# VREG_RT9166-13PVL_with_EN.net
KiCad netlist of a schematic drawn in Altium Designer
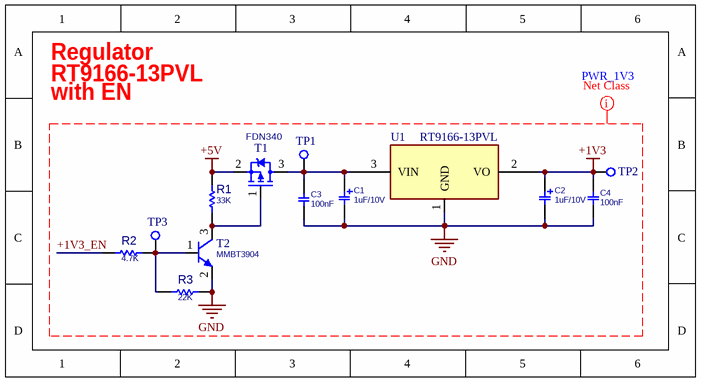
[diagram p0: VREG RT9166-13PVL with EN.SchDoc]

(export (version "E")
  (design (tool "Eeschema 10.0.6"))
  (components
    (comp (ref "C1")
      (value "1uF/10V")
      (footprint "C_TN_A")
      (description "CAP, SMD, TAN")
      (libsource (lib "PW Components 97_492") (part "CAP_SMD_TAN"))
    )
    (comp (ref "C2")
      (value "1uF/10V")
      (footprint "C_TN_A")
      (description "CAP, SMD, TAN")
      (libsource (lib "PW Components 97_492") (part "CAP_SMD_TAN"))
    )
    (comp (ref "C3")
      (value "100nF")
      (footprint "C0603S")
      (description "CAP, SMD, MLCC")
      (fields (field (name "MANF_P#") "MANF_PART#") (field (name "MANF") "Murata"))
      (libsource (lib "Passive") (part "CAP_SMD_MLCC"))
    )
    (comp (ref "C4")
      (value "100nF")
      (footprint "C0603S")
      (description "CAP, SMD, MLCC")
      (fields (field (name "MANF_P#") "MANF_PART#") (field (name "MANF") "Murata"))
      (libsource (lib "Passive") (part "CAP_SMD_MLCC"))
    )
    (comp (ref "R1")
      (value "33K")
      (footprint "R0603S")
      (description "RES, SMD")
      (fields (field (name "MANF_P#") "RK73H1ETTP4701F") (field (name "MANF") "KOA SPEER"))
      (libsource (lib "Passive") (part "RES_SMD"))
    )
    (comp (ref "R2")
      (value "4.7K")
      (footprint "R0603S")
      (description "RES, SMD")
      (fields (field (name "MANF_P#") "RK73H1ETTP4701F") (field (name "MANF") "KOA SPEER"))
      (libsource (lib "Passive") (part "RES_SMD"))
    )
    (comp (ref "R3")
      (value "22K")
      (footprint "R0603S")
      (description "RES, SMD")
      (fields (field (name "MANF_P#") "RK73H1ETTP4701F") (field (name "MANF") "KOA SPEER"))
      (libsource (lib "Passive") (part "RES_SMD"))
    )
    (comp (ref "T1")
      (value "FDN340")
      (footprint "SOT23_3")
      (description "MOSFET SMD P-CH 20V 2A")
      (fields (field (name "MANF_P#") "FDN360"))
      (libsource (lib "Transistor FET") (part "MOSP_FDN340_SOT23"))
    )
    (comp (ref "T2")
      (value "MMBT3904")
      (footprint "SOT23_3")
      (description "BJT, NPN, 40V, 0.2A, SMD, SOT23")
      (fields (field (name "MANF") "Diodes, NXP, FAIRCHILD, ON"))
      (libsource (lib "Transistor BJT") (part "NPN_MMBT3904_SOT23"))
    )
    (comp (ref "TP1")
      (value "Test Point")
      (footprint "TPSMD_C1")
      (libsource (lib "Passives") (part "Test Point"))
    )
    (comp (ref "TP2")
      (value "Test Point")
      (footprint "TPSMD_C1")
      (libsource (lib "Passives") (part "Test Point"))
    )
    (comp (ref "TP3")
      (value "Test Point")
      (footprint "TPSMD_C1")
      (libsource (lib "Passives") (part "Test Point"))
    )
    (comp (ref "U1")
      (value "RT9166-13PVL")
      (footprint "SOT23_3")
      (description "REG, Linear, Fixed, 1.3v, 0.3A/0.6A, SOT23")
      (fields (field (name "MANF") "TI"))
      (libsource (lib "PW Components 97_481") (part "VREG_RT9166A-13PVL_SOT23"))
    )
  )
  (nets
    (net (code "1") (name "+1V3") (class "Default")
      (node (ref "C2") (pin "1") (pinfunction "1_1") (pintype "passive"))
      (node (ref "C4") (pin "1") (pinfunction "1_1") (pintype "passive"))
      (node (ref "TP2") (pin "1") (pinfunction "TP_1") (pintype "passive"))
      (node (ref "U1") (pin "2") (pinfunction "VO_2") (pintype "passive"))
    )
    (net (code "2") (name "+5V") (class "Default")
      (node (ref "R1") (pin "2") (pinfunction "2_2") (pintype "passive"))
      (node (ref "T1") (pin "2") (pinfunction "S_2") (pintype "passive"))
    )
    (net (code "3") (name "/+1V3_EN") (class "Default")
      (node (ref "R2") (pin "2") (pinfunction "2_2") (pintype "passive"))
    )
    (net (code "4") (name "GND") (class "Default")
      (node (ref "C1") (pin "2") (pinfunction "2_2") (pintype "passive"))
      (node (ref "C2") (pin "2") (pinfunction "2_2") (pintype "passive"))
      (node (ref "C3") (pin "2") (pinfunction "2_2") (pintype "passive"))
      (node (ref "C4") (pin "2") (pinfunction "2_2") (pintype "passive"))
      (node (ref "R3") (pin "1") (pinfunction "1_1") (pintype "passive"))
      (node (ref "T2") (pin "2") (pinfunction "E_2") (pintype "passive"))
      (node (ref "U1") (pin "1") (pinfunction "GND_1") (pintype "passive"))
    )
    (net (code "5") (name "Net-(T1-D)") (class "Default")
      (node (ref "C1") (pin "1") (pinfunction "1_1") (pintype "passive"))
      (node (ref "C3") (pin "1") (pinfunction "1_1") (pintype "passive"))
      (node (ref "T1") (pin "3") (pinfunction "D_3") (pintype "passive"))
      (node (ref "TP1") (pin "1") (pinfunction "TP_1") (pintype "passive"))
      (node (ref "U1") (pin "3") (pinfunction "VIN_3") (pintype "passive"))
    )
    (net (code "6") (name "Net-(T1-G)") (class "Default")
      (node (ref "R1") (pin "1") (pinfunction "1_1") (pintype "passive"))
      (node (ref "T1") (pin "1") (pinfunction "G_1") (pintype "passive"))
      (node (ref "T2") (pin "3") (pinfunction "C_3") (pintype "passive"))
    )
    (net (code "7") (name "Net-(T2-B)") (class "Default")
      (node (ref "R2") (pin "1") (pinfunction "1_1") (pintype "passive"))
      (node (ref "R3") (pin "2") (pinfunction "2_2") (pintype "passive"))
      (node (ref "T2") (pin "1") (pinfunction "B_1") (pintype "passive"))
      (node (ref "TP3") (pin "1") (pinfunction "TP_1") (pintype "passive"))
    )
  )
)
